# ws2812_copy.net
KiCad netlist of a schematic drawn in Altium Designer
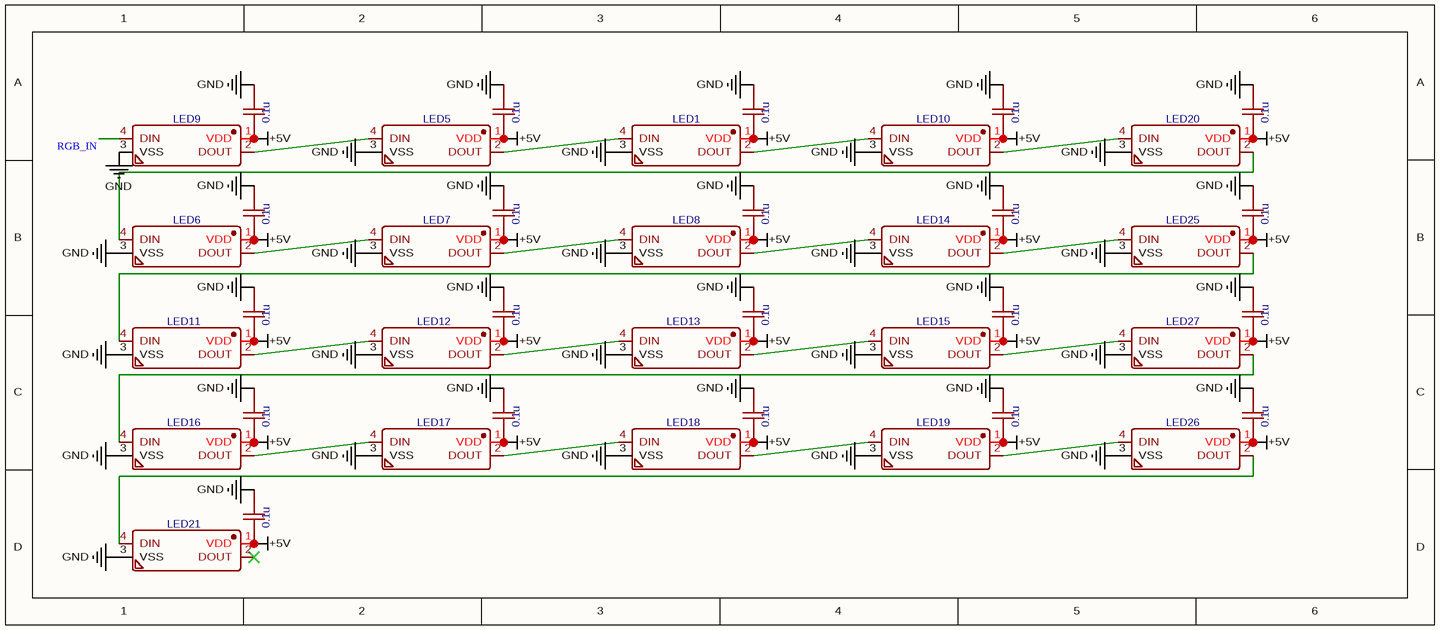
[diagram p0: ws2812 copy.schdoc]

(export (version "E")
  (design (tool "Eeschema 10.0.6"))
  (components
    (comp (ref "C1")
      (value "0.1u")
      (fields (field (name "CONTRIBUTOR") "LCEDA_Lib"))
      (libsource (lib "altium-import") (part "root_1_0.1u_"))
    )
    (comp (ref "C3")
      (value "0.1u")
      (fields (field (name "CONTRIBUTOR") "LCEDA_Lib"))
      (libsource (lib "altium-import") (part "root_1_0.1u_"))
    )
    (comp (ref "C6")
      (value "0.1u")
      (fields (field (name "CONTRIBUTOR") "LCEDA_Lib"))
      (libsource (lib "altium-import") (part "root_1_0.1u_"))
    )
    (comp (ref "C22")
      (value "0.1u")
      (fields (field (name "CONTRIBUTOR") "LCEDA_Lib"))
      (libsource (lib "altium-import") (part "root_1_0.1u_"))
    )
    (comp (ref "C25")
      (value "0.1u")
      (fields (field (name "CONTRIBUTOR") "LCEDA_Lib"))
      (libsource (lib "altium-import") (part "root_1_0.1u_"))
    )
    (comp (ref "C26")
      (value "0.1u")
      (fields (field (name "CONTRIBUTOR") "LCEDA_Lib"))
      (libsource (lib "altium-import") (part "root_1_0.1u_"))
    )
    (comp (ref "C27")
      (value "0.1u")
      (fields (field (name "CONTRIBUTOR") "LCEDA_Lib"))
      (libsource (lib "altium-import") (part "root_1_0.1u_"))
    )
    (comp (ref "C28")
      (value "0.1u")
      (fields (field (name "CONTRIBUTOR") "LCEDA_Lib"))
      (libsource (lib "altium-import") (part "root_1_0.1u_"))
    )
    (comp (ref "C29")
      (value "0.1u")
      (fields (field (name "CONTRIBUTOR") "LCEDA_Lib"))
      (libsource (lib "altium-import") (part "root_1_0.1u_"))
    )
    (comp (ref "C30")
      (value "0.1u")
      (fields (field (name "CONTRIBUTOR") "LCEDA_Lib"))
      (libsource (lib "altium-import") (part "root_1_0.1u_"))
    )
    (comp (ref "C31")
      (value "0.1u")
      (fields (field (name "CONTRIBUTOR") "LCEDA_Lib"))
      (libsource (lib "altium-import") (part "root_1_0.1u_"))
    )
    (comp (ref "C32")
      (value "0.1u")
      (fields (field (name "CONTRIBUTOR") "LCEDA_Lib"))
      (libsource (lib "altium-import") (part "root_1_0.1u_"))
    )
    (comp (ref "C33")
      (value "0.1u")
      (fields (field (name "CONTRIBUTOR") "LCEDA_Lib"))
      (libsource (lib "altium-import") (part "root_1_0.1u_"))
    )
    (comp (ref "C34")
      (value "0.1u")
      (fields (field (name "CONTRIBUTOR") "LCEDA_Lib"))
      (libsource (lib "altium-import") (part "root_1_0.1u_"))
    )
    (comp (ref "C35")
      (value "0.1u")
      (fields (field (name "CONTRIBUTOR") "LCEDA_Lib"))
      (libsource (lib "altium-import") (part "root_1_0.1u_"))
    )
    (comp (ref "C36")
      (value "0.1u")
      (fields (field (name "CONTRIBUTOR") "LCEDA_Lib"))
      (libsource (lib "altium-import") (part "root_1_0.1u_"))
    )
    (comp (ref "C37")
      (value "0.1u")
      (fields (field (name "CONTRIBUTOR") "LCEDA_Lib"))
      (libsource (lib "altium-import") (part "root_1_0.1u_"))
    )
    (comp (ref "C39")
      (value "0.1u")
      (fields (field (name "CONTRIBUTOR") "LCEDA_Lib"))
      (libsource (lib "altium-import") (part "root_1_0.1u_"))
    )
    (comp (ref "C40")
      (value "0.1u")
      (fields (field (name "CONTRIBUTOR") "LCEDA_Lib"))
      (libsource (lib "altium-import") (part "root_1_0.1u_"))
    )
    (comp (ref "C41")
      (value "0.1u")
      (fields (field (name "CONTRIBUTOR") "LCEDA_Lib"))
      (libsource (lib "altium-import") (part "root_1_0.1u_"))
    )
    (comp (ref "C42")
      (value "0.1u")
      (fields (field (name "CONTRIBUTOR") "LCEDA_Lib"))
      (libsource (lib "altium-import") (part "root_1_0.1u_"))
    )
    (comp (ref "LED1")
      (value "WS2812E")
      (fields (field (name "BOM_SUPPLIER PART") "C139127") (field (name "CONTRIBUTOR") "LCSC"))
      (libsource (lib "altium-import") (part "root_0_WS2812E_"))
    )
    (comp (ref "LED5")
      (value "WS2812E")
      (fields (field (name "BOM_SUPPLIER PART") "C139127") (field (name "CONTRIBUTOR") "LCSC"))
      (libsource (lib "altium-import") (part "root_0_WS2812E_"))
    )
    (comp (ref "LED6")
      (value "WS2812E")
      (fields (field (name "BOM_SUPPLIER PART") "C139127") (field (name "CONTRIBUTOR") "LCSC"))
      (libsource (lib "altium-import") (part "root_0_WS2812E_"))
    )
    (comp (ref "LED7")
      (value "WS2812E")
      (fields (field (name "BOM_SUPPLIER PART") "C139127") (field (name "CONTRIBUTOR") "LCSC"))
      (libsource (lib "altium-import") (part "root_0_WS2812E_"))
    )
    (comp (ref "LED8")
      (value "WS2812E")
      (fields (field (name "BOM_SUPPLIER PART") "C139127") (field (name "CONTRIBUTOR") "LCSC"))
      (libsource (lib "altium-import") (part "root_0_WS2812E_"))
    )
    (comp (ref "LED9")
      (value "WS2812E")
      (fields (field (name "BOM_SUPPLIER PART") "C139127") (field (name "CONTRIBUTOR") "LCSC"))
      (libsource (lib "altium-import") (part "root_0_WS2812E_"))
    )
    (comp (ref "LED10")
      (value "WS2812E")
      (fields (field (name "BOM_SUPPLIER PART") "C139127") (field (name "CONTRIBUTOR") "LCSC"))
      (libsource (lib "altium-import") (part "root_0_WS2812E_"))
    )
    (comp (ref "LED11")
      (value "WS2812E")
      (fields (field (name "BOM_SUPPLIER PART") "C139127") (field (name "CONTRIBUTOR") "LCSC"))
      (libsource (lib "altium-import") (part "root_0_WS2812E_"))
    )
    (comp (ref "LED12")
      (value "WS2812E")
      (fields (field (name "BOM_SUPPLIER PART") "C139127") (field (name "CONTRIBUTOR") "LCSC"))
      (libsource (lib "altium-import") (part "root_0_WS2812E_"))
    )
    (comp (ref "LED13")
      (value "WS2812E")
      (fields (field (name "BOM_SUPPLIER PART") "C139127") (field (name "CONTRIBUTOR") "LCSC"))
      (libsource (lib "altium-import") (part "root_0_WS2812E_"))
    )
    (comp (ref "LED14")
      (value "WS2812E")
      (fields (field (name "BOM_SUPPLIER PART") "C139127") (field (name "CONTRIBUTOR") "LCSC"))
      (libsource (lib "altium-import") (part "root_0_WS2812E_"))
    )
    (comp (ref "LED15")
      (value "WS2812E")
      (fields (field (name "BOM_SUPPLIER PART") "C139127") (field (name "CONTRIBUTOR") "LCSC"))
      (libsource (lib "altium-import") (part "root_0_WS2812E_"))
    )
    (comp (ref "LED16")
      (value "WS2812E")
      (fields (field (name "BOM_SUPPLIER PART") "C139127") (field (name "CONTRIBUTOR") "LCSC"))
      (libsource (lib "altium-import") (part "root_0_WS2812E_"))
    )
    (comp (ref "LED17")
      (value "WS2812E")
      (fields (field (name "BOM_SUPPLIER PART") "C139127") (field (name "CONTRIBUTOR") "LCSC"))
      (libsource (lib "altium-import") (part "root_0_WS2812E_"))
    )
    (comp (ref "LED18")
      (value "WS2812E")
      (fields (field (name "BOM_SUPPLIER PART") "C139127") (field (name "CONTRIBUTOR") "LCSC"))
      (libsource (lib "altium-import") (part "root_0_WS2812E_"))
    )
    (comp (ref "LED19")
      (value "WS2812E")
      (fields (field (name "BOM_SUPPLIER PART") "C139127") (field (name "CONTRIBUTOR") "LCSC"))
      (libsource (lib "altium-import") (part "root_0_WS2812E_"))
    )
    (comp (ref "LED20")
      (value "WS2812E")
      (fields (field (name "BOM_SUPPLIER PART") "C139127") (field (name "CONTRIBUTOR") "LCSC"))
      (libsource (lib "altium-import") (part "root_0_WS2812E_"))
    )
    (comp (ref "LED21")
      (value "WS2812E")
      (fields (field (name "BOM_SUPPLIER PART") "C139127") (field (name "CONTRIBUTOR") "LCSC"))
      (libsource (lib "altium-import") (part "root_0_WS2812E_"))
    )
    (comp (ref "LED25")
      (value "WS2812E")
      (fields (field (name "BOM_SUPPLIER PART") "C139127") (field (name "CONTRIBUTOR") "LCSC"))
      (libsource (lib "altium-import") (part "root_0_WS2812E_"))
    )
    (comp (ref "LED26")
      (value "WS2812E")
      (fields (field (name "BOM_SUPPLIER PART") "C139127") (field (name "CONTRIBUTOR") "LCSC"))
      (libsource (lib "altium-import") (part "root_0_WS2812E_"))
    )
    (comp (ref "LED27")
      (value "WS2812E")
      (fields (field (name "BOM_SUPPLIER PART") "C139127") (field (name "CONTRIBUTOR") "LCSC"))
      (libsource (lib "altium-import") (part "root_0_WS2812E_"))
    )
  )
  (nets
    (net (code "1") (name "+5V") (class "Default")
      (node (ref "C1") (pin "1") (pinfunction "1_1") (pintype "passive"))
      (node (ref "C22") (pin "1") (pinfunction "1_1") (pintype "passive"))
      (node (ref "C25") (pin "1") (pinfunction "1_1") (pintype "passive"))
      (node (ref "C26") (pin "1") (pinfunction "1_1") (pintype "passive"))
      (node (ref "C27") (pin "1") (pinfunction "1_1") (pintype "passive"))
      (node (ref "C28") (pin "1") (pinfunction "1_1") (pintype "passive"))
      (node (ref "C29") (pin "1") (pinfunction "1_1") (pintype "passive"))
      (node (ref "C3") (pin "1") (pinfunction "1_1") (pintype "passive"))
      (node (ref "C30") (pin "1") (pinfunction "1_1") (pintype "passive"))
      (node (ref "C31") (pin "1") (pinfunction "1_1") (pintype "passive"))
      (node (ref "C32") (pin "1") (pinfunction "1_1") (pintype "passive"))
      (node (ref "C33") (pin "1") (pinfunction "1_1") (pintype "passive"))
      (node (ref "C34") (pin "1") (pinfunction "1_1") (pintype "passive"))
      (node (ref "C35") (pin "1") (pinfunction "1_1") (pintype "passive"))
      (node (ref "C36") (pin "1") (pinfunction "1_1") (pintype "passive"))
      (node (ref "C37") (pin "1") (pinfunction "1_1") (pintype "passive"))
      (node (ref "C39") (pin "1") (pinfunction "1_1") (pintype "passive"))
      (node (ref "C40") (pin "1") (pinfunction "1_1") (pintype "passive"))
      (node (ref "C41") (pin "1") (pinfunction "1_1") (pintype "passive"))
      (node (ref "C42") (pin "1") (pinfunction "1_1") (pintype "passive"))
      (node (ref "C6") (pin "1") (pinfunction "1_1") (pintype "passive"))
      (node (ref "LED1") (pin "1") (pinfunction "VDD_1") (pintype "passive"))
      (node (ref "LED10") (pin "1") (pinfunction "VDD_1") (pintype "passive"))
      (node (ref "LED11") (pin "1") (pinfunction "VDD_1") (pintype "passive"))
      (node (ref "LED12") (pin "1") (pinfunction "VDD_1") (pintype "passive"))
      (node (ref "LED13") (pin "1") (pinfunction "VDD_1") (pintype "passive"))
      (node (ref "LED14") (pin "1") (pinfunction "VDD_1") (pintype "passive"))
      (node (ref "LED15") (pin "1") (pinfunction "VDD_1") (pintype "passive"))
      (node (ref "LED16") (pin "1") (pinfunction "VDD_1") (pintype "passive"))
      (node (ref "LED17") (pin "1") (pinfunction "VDD_1") (pintype "passive"))
      (node (ref "LED18") (pin "1") (pinfunction "VDD_1") (pintype "passive"))
      (node (ref "LED19") (pin "1") (pinfunction "VDD_1") (pintype "passive"))
      (node (ref "LED20") (pin "1") (pinfunction "VDD_1") (pintype "passive"))
      (node (ref "LED21") (pin "1") (pinfunction "VDD_1") (pintype "passive"))
      (node (ref "LED25") (pin "1") (pinfunction "VDD_1") (pintype "passive"))
      (node (ref "LED26") (pin "1") (pinfunction "VDD_1") (pintype "passive"))
      (node (ref "LED27") (pin "1") (pinfunction "VDD_1") (pintype "passive"))
      (node (ref "LED5") (pin "1") (pinfunction "VDD_1") (pintype "passive"))
      (node (ref "LED6") (pin "1") (pinfunction "VDD_1") (pintype "passive"))
      (node (ref "LED7") (pin "1") (pinfunction "VDD_1") (pintype "passive"))
      (node (ref "LED8") (pin "1") (pinfunction "VDD_1") (pintype "passive"))
      (node (ref "LED9") (pin "1") (pinfunction "VDD_1") (pintype "passive"))
    )
    (net (code "2") (name "/RGB_IN") (class "Default")
      (node (ref "LED9") (pin "4") (pinfunction "DIN_4") (pintype "passive"))
    )
    (net (code "3") (name "GND") (class "Default")
      (node (ref "C1") (pin "2") (pinfunction "2_2") (pintype "passive"))
      (node (ref "C22") (pin "2") (pinfunction "2_2") (pintype "passive"))
      (node (ref "C25") (pin "2") (pinfunction "2_2") (pintype "passive"))
      (node (ref "C26") (pin "2") (pinfunction "2_2") (pintype "passive"))
      (node (ref "C27") (pin "2") (pinfunction "2_2") (pintype "passive"))
      (node (ref "C28") (pin "2") (pinfunction "2_2") (pintype "passive"))
      (node (ref "C29") (pin "2") (pinfunction "2_2") (pintype "passive"))
      (node (ref "C3") (pin "2") (pinfunction "2_2") (pintype "passive"))
      (node (ref "C30") (pin "2") (pinfunction "2_2") (pintype "passive"))
      (node (ref "C31") (pin "2") (pinfunction "2_2") (pintype "passive"))
      (node (ref "C32") (pin "2") (pinfunction "2_2") (pintype "passive"))
      (node (ref "C33") (pin "2") (pinfunction "2_2") (pintype "passive"))
      (node (ref "C34") (pin "2") (pinfunction "2_2") (pintype "passive"))
      (node (ref "C35") (pin "2") (pinfunction "2_2") (pintype "passive"))
      (node (ref "C36") (pin "2") (pinfunction "2_2") (pintype "passive"))
      (node (ref "C37") (pin "2") (pinfunction "2_2") (pintype "passive"))
      (node (ref "C39") (pin "2") (pinfunction "2_2") (pintype "passive"))
      (node (ref "C40") (pin "2") (pinfunction "2_2") (pintype "passive"))
      (node (ref "C41") (pin "2") (pinfunction "2_2") (pintype "passive"))
      (node (ref "C42") (pin "2") (pinfunction "2_2") (pintype "passive"))
      (node (ref "C6") (pin "2") (pinfunction "2_2") (pintype "passive"))
      (node (ref "LED1") (pin "3") (pinfunction "VSS_3") (pintype "passive"))
      (node (ref "LED10") (pin "3") (pinfunction "VSS_3") (pintype "passive"))
      (node (ref "LED11") (pin "3") (pinfunction "VSS_3") (pintype "passive"))
      (node (ref "LED12") (pin "3") (pinfunction "VSS_3") (pintype "passive"))
      (node (ref "LED13") (pin "3") (pinfunction "VSS_3") (pintype "passive"))
      (node (ref "LED14") (pin "3") (pinfunction "VSS_3") (pintype "passive"))
      (node (ref "LED15") (pin "3") (pinfunction "VSS_3") (pintype "passive"))
      (node (ref "LED16") (pin "3") (pinfunction "VSS_3") (pintype "passive"))
      (node (ref "LED17") (pin "3") (pinfunction "VSS_3") (pintype "passive"))
      (node (ref "LED18") (pin "3") (pinfunction "VSS_3") (pintype "passive"))
      (node (ref "LED19") (pin "3") (pinfunction "VSS_3") (pintype "passive"))
      (node (ref "LED20") (pin "3") (pinfunction "VSS_3") (pintype "passive"))
      (node (ref "LED21") (pin "3") (pinfunction "VSS_3") (pintype "passive"))
      (node (ref "LED25") (pin "3") (pinfunction "VSS_3") (pintype "passive"))
      (node (ref "LED26") (pin "3") (pinfunction "VSS_3") (pintype "passive"))
      (node (ref "LED27") (pin "3") (pinfunction "VSS_3") (pintype "passive"))
      (node (ref "LED5") (pin "3") (pinfunction "VSS_3") (pintype "passive"))
      (node (ref "LED6") (pin "3") (pinfunction "VSS_3") (pintype "passive"))
      (node (ref "LED7") (pin "3") (pinfunction "VSS_3") (pintype "passive"))
      (node (ref "LED8") (pin "3") (pinfunction "VSS_3") (pintype "passive"))
      (node (ref "LED9") (pin "3") (pinfunction "VSS_3") (pintype "passive"))
    )
    (net (code "4") (name "Net-(LED1-DIN)") (class "Default")
      (node (ref "LED1") (pin "4") (pinfunction "DIN_4") (pintype "passive"))
      (node (ref "LED5") (pin "2") (pinfunction "DOUT_2") (pintype "passive"))
    )
    (net (code "5") (name "Net-(LED1-DOUT)") (class "Default")
      (node (ref "LED1") (pin "2") (pinfunction "DOUT_2") (pintype "passive"))
      (node (ref "LED10") (pin "4") (pinfunction "DIN_4") (pintype "passive"))
    )
    (net (code "6") (name "Net-(LED5-DIN)") (class "Default")
      (node (ref "LED5") (pin "4") (pinfunction "DIN_4") (pintype "passive"))
      (node (ref "LED9") (pin "2") (pinfunction "DOUT_2") (pintype "passive"))
    )
    (net (code "7") (name "Net-(LED6-DOUT)") (class "Default")
      (node (ref "LED6") (pin "2") (pinfunction "DOUT_2") (pintype "passive"))
      (node (ref "LED7") (pin "4") (pinfunction "DIN_4") (pintype "passive"))
    )
    (net (code "8") (name "Net-(LED7-DOUT)") (class "Default")
      (node (ref "LED7") (pin "2") (pinfunction "DOUT_2") (pintype "passive"))
      (node (ref "LED8") (pin "4") (pinfunction "DIN_4") (pintype "passive"))
    )
    (net (code "9") (name "Net-(LED10-DOUT)") (class "Default")
      (node (ref "LED10") (pin "2") (pinfunction "DOUT_2") (pintype "passive"))
      (node (ref "LED20") (pin "4") (pinfunction "DIN_4") (pintype "passive"))
    )
    (net (code "10") (name "Net-(LED11-DIN)") (class "Default")
      (node (ref "LED11") (pin "4") (pinfunction "DIN_4") (pintype "passive"))
      (node (ref "LED25") (pin "2") (pinfunction "DOUT_2") (pintype "passive"))
    )
    (net (code "11") (name "Net-(LED11-DOUT)") (class "Default")
      (node (ref "LED11") (pin "2") (pinfunction "DOUT_2") (pintype "passive"))
      (node (ref "LED12") (pin "4") (pinfunction "DIN_4") (pintype "passive"))
    )
    (net (code "12") (name "Net-(LED12-DOUT)") (class "Default")
      (node (ref "LED12") (pin "2") (pinfunction "DOUT_2") (pintype "passive"))
      (node (ref "LED13") (pin "4") (pinfunction "DIN_4") (pintype "passive"))
    )
    (net (code "13") (name "Net-(LED13-DOUT)") (class "Default")
      (node (ref "LED13") (pin "2") (pinfunction "DOUT_2") (pintype "passive"))
      (node (ref "LED15") (pin "4") (pinfunction "DIN_4") (pintype "passive"))
    )
    (net (code "14") (name "Net-(LED14-DIN)") (class "Default")
      (node (ref "LED14") (pin "4") (pinfunction "DIN_4") (pintype "passive"))
      (node (ref "LED8") (pin "2") (pinfunction "DOUT_2") (pintype "passive"))
    )
    (net (code "15") (name "Net-(LED14-DOUT)") (class "Default")
      (node (ref "LED14") (pin "2") (pinfunction "DOUT_2") (pintype "passive"))
      (node (ref "LED25") (pin "4") (pinfunction "DIN_4") (pintype "passive"))
    )
    (net (code "16") (name "Net-(LED15-DOUT)") (class "Default")
      (node (ref "LED15") (pin "2") (pinfunction "DOUT_2") (pintype "passive"))
      (node (ref "LED27") (pin "4") (pinfunction "DIN_4") (pintype "passive"))
    )
    (net (code "17") (name "Net-(LED16-DIN)") (class "Default")
      (node (ref "LED16") (pin "4") (pinfunction "DIN_4") (pintype "passive"))
      (node (ref "LED27") (pin "2") (pinfunction "DOUT_2") (pintype "passive"))
    )
    (net (code "18") (name "Net-(LED16-DOUT)") (class "Default")
      (node (ref "LED16") (pin "2") (pinfunction "DOUT_2") (pintype "passive"))
      (node (ref "LED17") (pin "4") (pinfunction "DIN_4") (pintype "passive"))
    )
    (net (code "19") (name "Net-(LED17-DOUT)") (class "Default")
      (node (ref "LED17") (pin "2") (pinfunction "DOUT_2") (pintype "passive"))
      (node (ref "LED18") (pin "4") (pinfunction "DIN_4") (pintype "passive"))
    )
    (net (code "20") (name "Net-(LED18-DOUT)") (class "Default")
      (node (ref "LED18") (pin "2") (pinfunction "DOUT_2") (pintype "passive"))
      (node (ref "LED19") (pin "4") (pinfunction "DIN_4") (pintype "passive"))
    )
    (net (code "21") (name "Net-(LED19-DOUT)") (class "Default")
      (node (ref "LED19") (pin "2") (pinfunction "DOUT_2") (pintype "passive"))
      (node (ref "LED26") (pin "4") (pinfunction "DIN_4") (pintype "passive"))
    )
    (net (code "22") (name "Net-(LED20-DOUT)") (class "Default")
      (node (ref "LED20") (pin "2") (pinfunction "DOUT_2") (pintype "passive"))
      (node (ref "LED6") (pin "4") (pinfunction "DIN_4") (pintype "passive"))
    )
    (net (code "23") (name "Net-(LED21-DIN)") (class "Default")
      (node (ref "LED21") (pin "4") (pinfunction "DIN_4") (pintype "passive"))
      (node (ref "LED26") (pin "2") (pinfunction "DOUT_2") (pintype "passive"))
    )
    (net (code "24") (name "unconnected-(LED21-DOUT-Pad2)") (class "Default")
      (node (ref "LED21") (pin "2") (pinfunction "DOUT_2") (pintype "passive+no_connect"))
    )
  )
)
